# atxmega64.net
KiCad netlist of a schematic drawn in Altium Designer
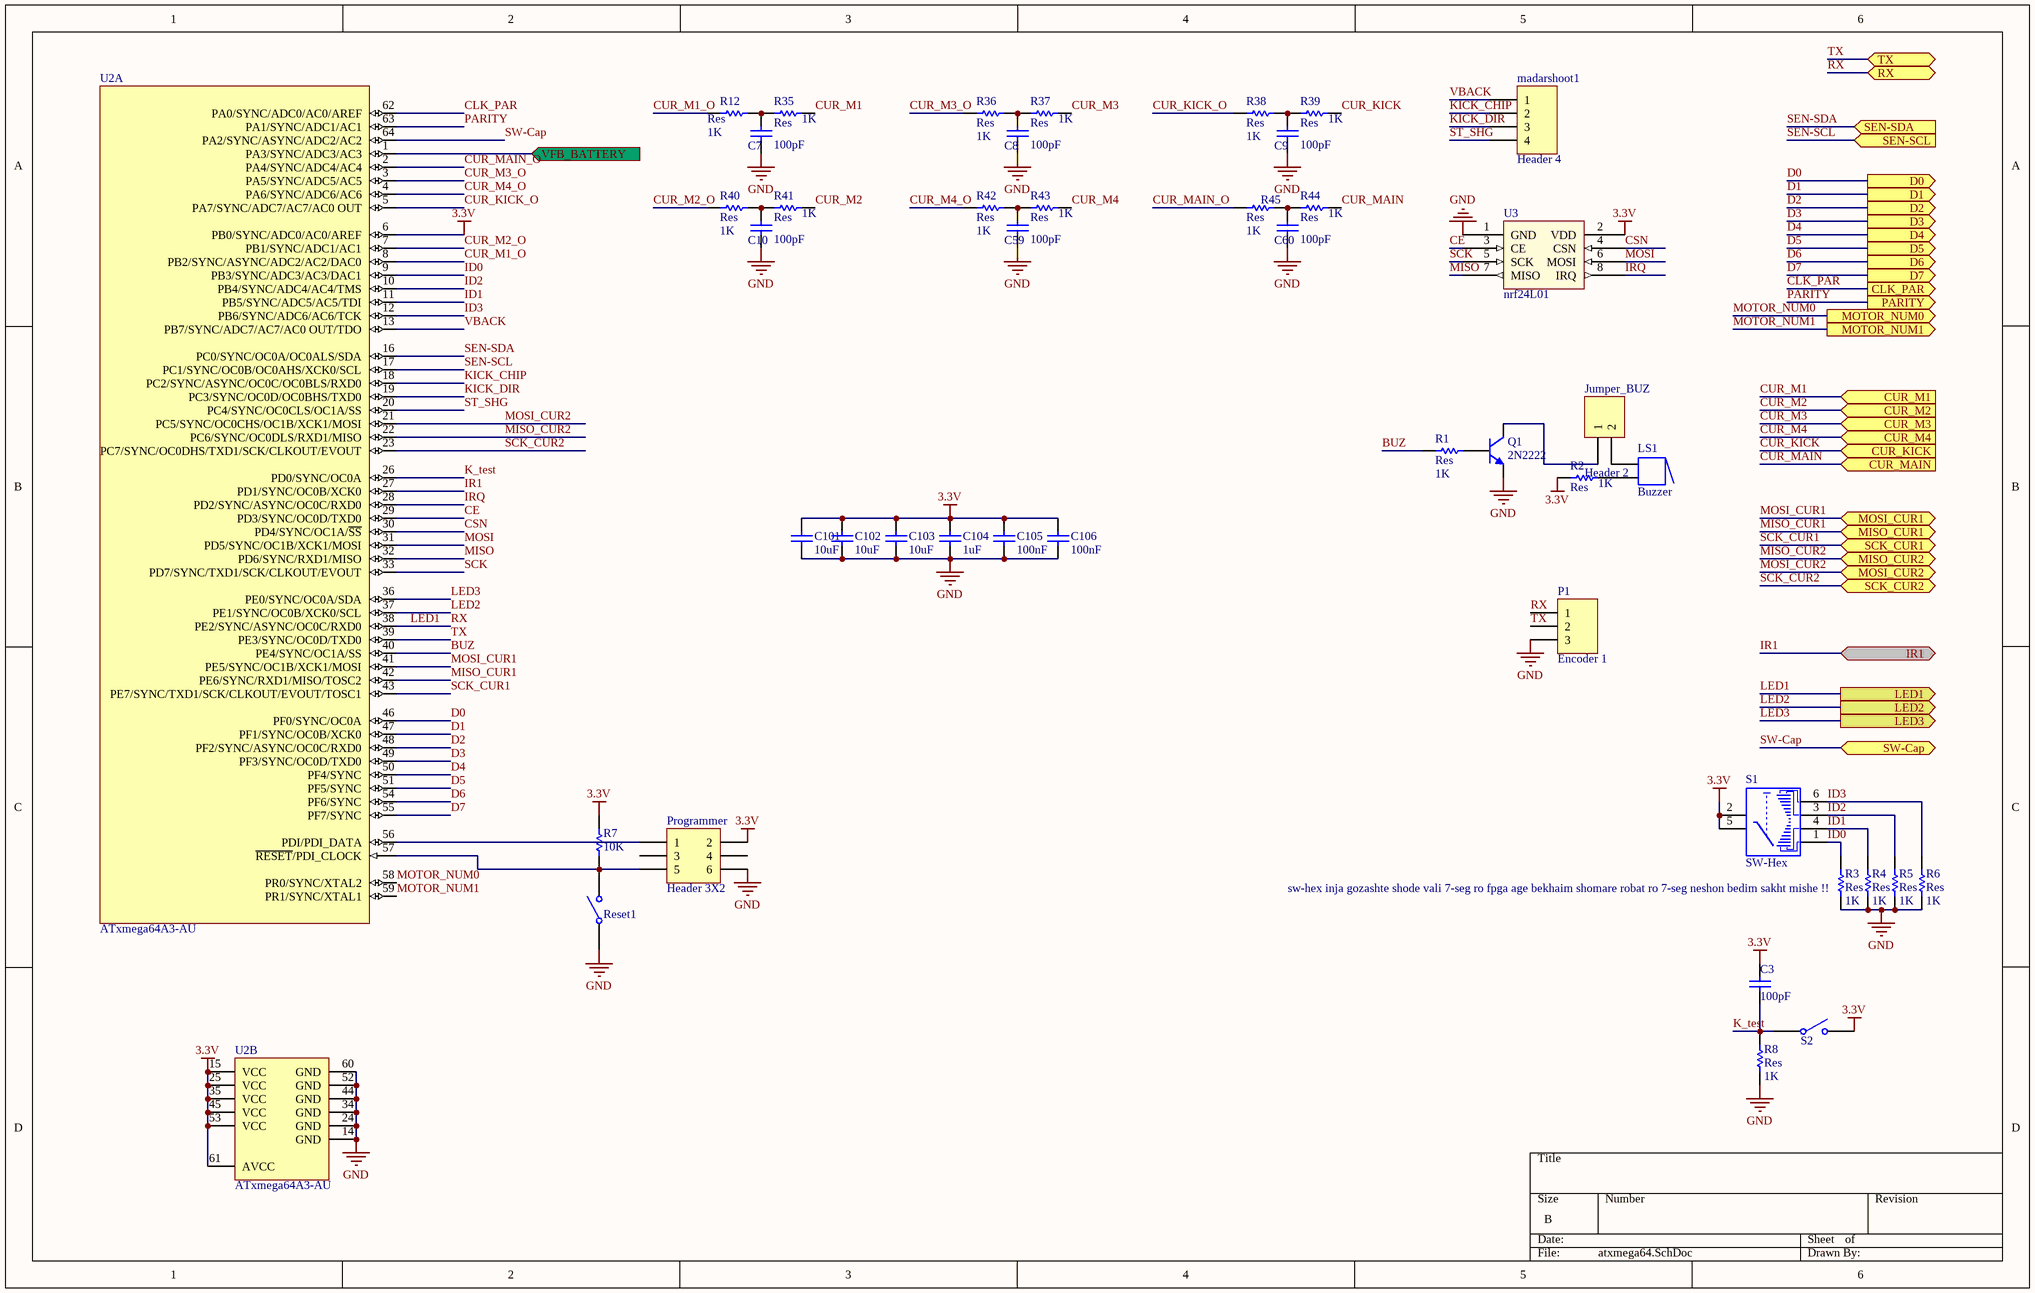
[diagram p0: atxmega64.SchDoc]

(export (version "E")
  (design (tool "Eeschema 10.0.6"))
  (components
    (comp (ref "C3")
      (value "100pF")
      (footprint "2012[0805]")
      (description "Capacitor")
      (fields (field (name "Comment") "Cap_UP") (field (name "PUBLISHER") "Altium Limited"))
      (libsource (lib "KN2CLib") (part "Cap_UP"))
    )
    (comp (ref "C7")
      (value "100pF")
      (footprint "2012[0805]")
      (description "Capacitor")
      (fields (field (name "Comment") "Cap_UP") (field (name "PUBLISHER") "Altium Limited"))
      (libsource (lib "KN2CLib") (part "Cap_UP"))
    )
    (comp (ref "C8")
      (value "100pF")
      (footprint "2012[0805]")
      (description "Capacitor")
      (fields (field (name "Comment") "Cap_UP") (field (name "PUBLISHER") "Altium Limited"))
      (libsource (lib "KN2CLib") (part "Cap_UP"))
    )
    (comp (ref "C9")
      (value "100pF")
      (footprint "2012[0805]")
      (description "Capacitor")
      (fields (field (name "Comment") "Cap_UP") (field (name "PUBLISHER") "Altium Limited"))
      (libsource (lib "KN2CLib") (part "Cap_UP"))
    )
    (comp (ref "C10")
      (value "100pF")
      (footprint "2012[0805]")
      (description "Capacitor")
      (fields (field (name "Comment") "Cap_UP") (field (name "PUBLISHER") "Altium Limited"))
      (libsource (lib "KN2CLib") (part "Cap_UP"))
    )
    (comp (ref "C59")
      (value "100pF")
      (footprint "2012[0805]")
      (description "Capacitor")
      (fields (field (name "Comment") "Cap_UP") (field (name "PUBLISHER") "Altium Limited"))
      (libsource (lib "KN2CLib") (part "Cap_UP"))
    )
    (comp (ref "C60")
      (value "100pF")
      (footprint "2012[0805]")
      (description "Capacitor")
      (fields (field (name "Comment") "Cap_UP") (field (name "PUBLISHER") "Altium Limited"))
      (libsource (lib "KN2CLib") (part "Cap_UP"))
    )
    (comp (ref "C101")
      (value "10uF")
      (footprint "2012[0805]")
      (description "Capacitor")
      (fields (field (name "Comment") "Cap_UP") (field (name "PUBLISHER") "Altium Limited"))
      (libsource (lib "KN2CLib") (part "Cap_UP"))
    )
    (comp (ref "C102")
      (value "10uF")
      (footprint "2012[0805]")
      (description "Capacitor")
      (fields (field (name "Comment") "Cap_UP") (field (name "PUBLISHER") "Altium Limited"))
      (libsource (lib "KN2CLib") (part "Cap_UP"))
    )
    (comp (ref "C103")
      (value "10uF")
      (footprint "2012[0805]")
      (description "Capacitor")
      (fields (field (name "Comment") "Cap_UP") (field (name "PUBLISHER") "Altium Limited"))
      (libsource (lib "KN2CLib") (part "Cap_UP"))
    )
    (comp (ref "C104")
      (value "1uF")
      (footprint "2012[0805]")
      (description "Capacitor")
      (fields (field (name "Comment") "Cap_UP") (field (name "PUBLISHER") "Altium Limited"))
      (libsource (lib "KN2CLib") (part "Cap_UP"))
    )
    (comp (ref "C105")
      (value "100nF")
      (footprint "2012[0805]")
      (description "Capacitor")
      (fields (field (name "Comment") "Cap_UP") (field (name "PUBLISHER") "Altium Limited"))
      (libsource (lib "KN2CLib") (part "Cap_UP"))
    )
    (comp (ref "C106")
      (value "100nF")
      (footprint "2012[0805]")
      (description "Capacitor")
      (fields (field (name "Comment") "Cap_UP") (field (name "PUBLISHER") "Altium Limited"))
      (libsource (lib "KN2CLib") (part "Cap_UP"))
    )
    (comp (ref "Jumper_BUZ")
      (value "Header 2")
      (footprint "HDR1X2")
      (description "Header, 2-Pin")
      (fields (field (name "PUBLISHER") "Altium Limited"))
      (libsource (lib "Miscellaneous Connectors") (part "Header 2"))
    )
    (comp (ref "LS1")
      (value "Buzzer")
      (footprint "BUZZER")
      (description "Magnetic Transducer Buzzer")
      (fields (field (name "PUBLISHER") "Altium Limited"))
      (libsource (lib "KN2CLib") (part "Buzzer"))
    )
    (comp (ref "madarshoot1")
      (value "Header 4")
      (footprint "sucket-smd-4pin")
      (description "Header, 4-Pin")
      (fields (field (name "PUBLISHER") "Altium Limited"))
      (libsource (lib "KN2CLib") (part "Header 4"))
    )
    (comp (ref "P1")
      (value "Encoder 1")
      (footprint "HDR1X3A")
      (description "Header, 3-Pin")
      (fields (field (name "PUBLISHER") "Altium Limited"))
      (libsource (lib "KN2CLib") (part "Header 3"))
    )
    (comp (ref "Programmer")
      (value "Header 3X2")
      (footprint "HDRBOX2X3")
      (description "Header, 3-Pin, Dual row")
      (fields (field (name "PUBLISHER") "Altium Limited"))
      (libsource (lib "KN2CLib") (part "Header 3X2"))
    )
    (comp (ref "Q1")
      (value "2N2222")
      (footprint "SOT-23")
      (description "NPN Bipolar Transistor")
      (fields (field (name "PUBLISHER") "Altium Limited"))
      (libsource (lib "KN2CLib") (part "2N2222"))
    )
    (comp (ref "R1")
      (value "Res")
      (footprint "2012[0805]")
      (description "Semiconductor Resistor")
      (fields (field (name "ALTIUM_VALUE") "1K") (field (name "PUBLISHER") "Altium Limited"))
      (libsource (lib "KN2CLib") (part "Res"))
    )
    (comp (ref "R2")
      (value "Res")
      (footprint "2012[0805]")
      (description "Semiconductor Resistor")
      (fields (field (name "ALTIUM_VALUE") "1K") (field (name "PUBLISHER") "Altium Limited"))
      (libsource (lib "KN2CLib") (part "Res"))
    )
    (comp (ref "R3")
      (value "Res")
      (footprint "2012[0805]")
      (description "Semiconductor Resistor")
      (fields (field (name "ALTIUM_VALUE") "1K") (field (name "PUBLISHER") "Altium Limited"))
      (libsource (lib "KN2CLib") (part "Res"))
    )
    (comp (ref "R4")
      (value "Res")
      (footprint "2012[0805]")
      (description "Semiconductor Resistor")
      (fields (field (name "ALTIUM_VALUE") "1K") (field (name "PUBLISHER") "Altium Limited"))
      (libsource (lib "KN2CLib") (part "Res"))
    )
    (comp (ref "R5")
      (value "Res")
      (footprint "2012[0805]")
      (description "Semiconductor Resistor")
      (fields (field (name "ALTIUM_VALUE") "1K") (field (name "PUBLISHER") "Altium Limited"))
      (libsource (lib "KN2CLib") (part "Res"))
    )
    (comp (ref "R6")
      (value "Res")
      (footprint "2012[0805]")
      (description "Semiconductor Resistor")
      (fields (field (name "ALTIUM_VALUE") "1K") (field (name "PUBLISHER") "Altium Limited"))
      (libsource (lib "KN2CLib") (part "Res"))
    )
    (comp (ref "R7")
      (value "10K")
      (footprint "2012[0805]")
      (description "Semiconductor Resistor")
      (fields (field (name "PUBLISHER") "Altium Limited"))
      (libsource (lib "KN2CLib") (part "Res"))
    )
    (comp (ref "R8")
      (value "Res")
      (footprint "2012[0805]")
      (description "Semiconductor Resistor")
      (fields (field (name "ALTIUM_VALUE") "1K") (field (name "PUBLISHER") "Altium Limited"))
      (libsource (lib "KN2CLib") (part "Res"))
    )
    (comp (ref "R12")
      (value "Res")
      (footprint "2012[0805]")
      (description "Semiconductor Resistor")
      (fields (field (name "ALTIUM_VALUE") "1K") (field (name "PUBLISHER") "Altium Limited"))
      (libsource (lib "KN2CLib") (part "Res"))
    )
    (comp (ref "R35")
      (value "Res")
      (footprint "2012[0805]")
      (description "Semiconductor Resistor")
      (fields (field (name "ALTIUM_VALUE") "1K") (field (name "PUBLISHER") "Altium Limited"))
      (libsource (lib "KN2CLib") (part "Res"))
    )
    (comp (ref "R36")
      (value "Res")
      (footprint "2012[0805]")
      (description "Semiconductor Resistor")
      (fields (field (name "ALTIUM_VALUE") "1K") (field (name "PUBLISHER") "Altium Limited"))
      (libsource (lib "KN2CLib") (part "Res"))
    )
    (comp (ref "R37")
      (value "Res")
      (footprint "2012[0805]")
      (description "Semiconductor Resistor")
      (fields (field (name "ALTIUM_VALUE") "1K") (field (name "PUBLISHER") "Altium Limited"))
      (libsource (lib "KN2CLib") (part "Res"))
    )
    (comp (ref "R38")
      (value "Res")
      (footprint "2012[0805]")
      (description "Semiconductor Resistor")
      (fields (field (name "ALTIUM_VALUE") "1K") (field (name "PUBLISHER") "Altium Limited"))
      (libsource (lib "KN2CLib") (part "Res"))
    )
    (comp (ref "R39")
      (value "Res")
      (footprint "2012[0805]")
      (description "Semiconductor Resistor")
      (fields (field (name "ALTIUM_VALUE") "1K") (field (name "PUBLISHER") "Altium Limited"))
      (libsource (lib "KN2CLib") (part "Res"))
    )
    (comp (ref "R40")
      (value "Res")
      (footprint "2012[0805]")
      (description "Semiconductor Resistor")
      (fields (field (name "ALTIUM_VALUE") "1K") (field (name "PUBLISHER") "Altium Limited"))
      (libsource (lib "KN2CLib") (part "Res"))
    )
    (comp (ref "R41")
      (value "Res")
      (footprint "2012[0805]")
      (description "Semiconductor Resistor")
      (fields (field (name "ALTIUM_VALUE") "1K") (field (name "PUBLISHER") "Altium Limited"))
      (libsource (lib "KN2CLib") (part "Res"))
    )
    (comp (ref "R42")
      (value "Res")
      (footprint "2012[0805]")
      (description "Semiconductor Resistor")
      (fields (field (name "ALTIUM_VALUE") "1K") (field (name "PUBLISHER") "Altium Limited"))
      (libsource (lib "KN2CLib") (part "Res"))
    )
    (comp (ref "R43")
      (value "Res")
      (footprint "2012[0805]")
      (description "Semiconductor Resistor")
      (fields (field (name "ALTIUM_VALUE") "1K") (field (name "PUBLISHER") "Altium Limited"))
      (libsource (lib "KN2CLib") (part "Res"))
    )
    (comp (ref "R44")
      (value "Res")
      (footprint "2012[0805]")
      (description "Semiconductor Resistor")
      (fields (field (name "ALTIUM_VALUE") "1K") (field (name "PUBLISHER") "Altium Limited"))
      (libsource (lib "KN2CLib") (part "Res"))
    )
    (comp (ref "R45")
      (value "Res")
      (footprint "2012[0805]")
      (description "Semiconductor Resistor")
      (fields (field (name "ALTIUM_VALUE") "1K") (field (name "PUBLISHER") "Altium Limited"))
      (libsource (lib "KN2CLib") (part "Res"))
    )
    (comp (ref "Reset1")
      (value "SW-SPST")
      (footprint "PUSH-BUT")
      (description "Single-Pole, Single-Throw Switch")
      (fields (field (name "PUBLISHER") "Altium Limited"))
      (libsource (lib "KN2CLib") (part "SW-SPST"))
    )
    (comp (ref "S1")
      (value "SW-Hex")
      (footprint "SW-HEX")
      (fields (field (name "PUBLISHER") "Altium Limited"))
      (libsource (lib "KN2CLib") (part "SW-Hex"))
    )
    (comp (ref "S2")
      (value "SW-SPST")
      (footprint "PUSH-BUT")
      (description "Single-Pole, Single-Throw Switch")
      (fields (field (name "PUBLISHER") "Altium Limited"))
      (libsource (lib "KN2CLib") (part "SW-SPST"))
    )
    (comp (ref "U2")
      (value "ATxmega64A3-AU")
      (footprint "64A_N")
      (fields (field (name "PUBLISHER") "Altium Limited"))
      (libsource (lib "Atmel Microcontroller 8-16-Bit AVR XMEGA") (part "ATxmega64A3-AU"))
    )
    (comp (ref "U3") (value "nrf24L01") (footprint "NRF24L01") (libsource (lib "KN2CLib") (part "nrf24L01")))
  )
  (nets
    (net (code "1") (name "/BUZ") (class "Default")
      (node (ref "R1") (pin "1") (pinfunction "1_1") (pintype "passive"))
      (node (ref "U2") (pin "40") (pinfunction "PE4/SYNC/OC1A/SS_40") (pintype "bidirectional"))
    )
    (net (code "2") (name "/CE") (class "Default")
      (node (ref "U2") (pin "29") (pinfunction "PD3/SYNC/OC0D/TXD0_29") (pintype "bidirectional"))
      (node (ref "U3") (pin "3") (pinfunction "CE_3") (pintype "input"))
    )
    (net (code "3") (name "/CLK_PAR") (class "Default")
      (node (ref "U2") (pin "62") (pinfunction "PA0/SYNC/ADC0/AC0/AREF_62") (pintype "bidirectional"))
    )
    (net (code "4") (name "/CSN") (class "Default")
      (node (ref "U2") (pin "30") (pinfunction "PD4/SYNC/OC1A/~{SS}_30") (pintype "bidirectional"))
      (node (ref "U3") (pin "4") (pinfunction "CSN_4") (pintype "input"))
    )
    (net (code "5") (name "/CUR_KICK") (class "Default")
      (node (ref "R39") (pin "2") (pinfunction "2_2") (pintype "passive"))
    )
    (net (code "6") (name "/CUR_KICK_O") (class "Default")
      (node (ref "R38") (pin "1") (pinfunction "1_1") (pintype "passive"))
      (node (ref "U2") (pin "5") (pinfunction "PA7/SYNC/ADC7/AC7/AC0_OUT_5") (pintype "bidirectional"))
    )
    (net (code "7") (name "/CUR_M1") (class "Default")
      (node (ref "R35") (pin "2") (pinfunction "2_2") (pintype "passive"))
    )
    (net (code "8") (name "/CUR_M1_O") (class "Default")
      (node (ref "R12") (pin "1") (pinfunction "1_1") (pintype "passive"))
      (node (ref "U2") (pin "8") (pinfunction "PB2/SYNC/ASYNC/ADC2/AC2/DAC0_8") (pintype "bidirectional"))
    )
    (net (code "9") (name "/CUR_M2") (class "Default")
      (node (ref "R41") (pin "2") (pinfunction "2_2") (pintype "passive"))
    )
    (net (code "10") (name "/CUR_M2_O") (class "Default")
      (node (ref "R40") (pin "1") (pinfunction "1_1") (pintype "passive"))
      (node (ref "U2") (pin "7") (pinfunction "PB1/SYNC/ADC1/AC1_7") (pintype "bidirectional"))
    )
    (net (code "11") (name "/CUR_M3") (class "Default")
      (node (ref "R37") (pin "2") (pinfunction "2_2") (pintype "passive"))
    )
    (net (code "12") (name "/CUR_M3_O") (class "Default")
      (node (ref "R36") (pin "1") (pinfunction "1_1") (pintype "passive"))
      (node (ref "U2") (pin "3") (pinfunction "PA5/SYNC/ADC5/AC5_3") (pintype "bidirectional"))
    )
    (net (code "13") (name "/CUR_M4") (class "Default")
      (node (ref "R43") (pin "2") (pinfunction "2_2") (pintype "passive"))
    )
    (net (code "14") (name "/CUR_M4_O") (class "Default")
      (node (ref "R42") (pin "1") (pinfunction "1_1") (pintype "passive"))
      (node (ref "U2") (pin "4") (pinfunction "PA6/SYNC/ADC6/AC6_4") (pintype "bidirectional"))
    )
    (net (code "15") (name "/CUR_MAIN") (class "Default")
      (node (ref "R44") (pin "2") (pinfunction "2_2") (pintype "passive"))
    )
    (net (code "16") (name "/CUR_MAIN_O") (class "Default")
      (node (ref "R45") (pin "1") (pinfunction "1_1") (pintype "passive"))
      (node (ref "U2") (pin "2") (pinfunction "PA4/SYNC/ADC4/AC4_2") (pintype "bidirectional"))
    )
    (net (code "17") (name "/D0") (class "Default")
      (node (ref "U2") (pin "46") (pinfunction "PF0/SYNC/OC0A_46") (pintype "bidirectional"))
    )
    (net (code "18") (name "/D1") (class "Default")
      (node (ref "U2") (pin "47") (pinfunction "PF1/SYNC/OC0B/XCK0_47") (pintype "bidirectional"))
    )
    (net (code "19") (name "/D2") (class "Default")
      (node (ref "U2") (pin "48") (pinfunction "PF2/SYNC/ASYNC/OC0C/RXD0_48") (pintype "bidirectional"))
    )
    (net (code "20") (name "/D3") (class "Default")
      (node (ref "U2") (pin "49") (pinfunction "PF3/SYNC/OC0D/TXD0_49") (pintype "bidirectional"))
    )
    (net (code "21") (name "/D4") (class "Default")
      (node (ref "U2") (pin "50") (pinfunction "PF4/SYNC_50") (pintype "bidirectional"))
    )
    (net (code "22") (name "/D5") (class "Default")
      (node (ref "U2") (pin "51") (pinfunction "PF5/SYNC_51") (pintype "bidirectional"))
    )
    (net (code "23") (name "/D6") (class "Default")
      (node (ref "U2") (pin "54") (pinfunction "PF6/SYNC_54") (pintype "bidirectional"))
    )
    (net (code "24") (name "/D7") (class "Default")
      (node (ref "U2") (pin "55") (pinfunction "PF7/SYNC_55") (pintype "bidirectional"))
    )
    (net (code "25") (name "/ID0") (class "Default")
      (node (ref "R3") (pin "2") (pinfunction "2_2") (pintype "passive"))
      (node (ref "S1") (pin "1") (pinfunction "1_1") (pintype "passive"))
      (node (ref "U2") (pin "9") (pinfunction "PB3/SYNC/ADC3/AC3/DAC1_9") (pintype "bidirectional"))
    )
    (net (code "26") (name "/ID1") (class "Default")
      (node (ref "R4") (pin "2") (pinfunction "2_2") (pintype "passive"))
      (node (ref "S1") (pin "4") (pinfunction "4_4") (pintype "passive"))
      (node (ref "U2") (pin "11") (pinfunction "PB5/SYNC/ADC5/AC5/TDI_11") (pintype "bidirectional"))
    )
    (net (code "27") (name "/ID2") (class "Default")
      (node (ref "R5") (pin "2") (pinfunction "2_2") (pintype "passive"))
      (node (ref "S1") (pin "3") (pinfunction "3_3") (pintype "passive"))
      (node (ref "U2") (pin "10") (pinfunction "PB4/SYNC/ADC4/AC4/TMS_10") (pintype "bidirectional"))
    )
    (net (code "28") (name "/ID3") (class "Default")
      (node (ref "R6") (pin "2") (pinfunction "2_2") (pintype "passive"))
      (node (ref "S1") (pin "6") (pinfunction "6_6") (pintype "passive"))
      (node (ref "U2") (pin "12") (pinfunction "PB6/SYNC/ADC6/AC6/TCK_12") (pintype "bidirectional"))
    )
    (net (code "29") (name "/IR1") (class "Default")
      (node (ref "U2") (pin "27") (pinfunction "PD1/SYNC/OC0B/XCK0_27") (pintype "bidirectional"))
    )
    (net (code "30") (name "/IRQ") (class "Default")
      (node (ref "U2") (pin "28") (pinfunction "PD2/SYNC/ASYNC/OC0C/RXD0_28") (pintype "bidirectional"))
      (node (ref "U3") (pin "8") (pinfunction "IRQ_8") (pintype "output"))
    )
    (net (code "31") (name "/KICK_CHIP") (class "Default")
      (node (ref "U2") (pin "18") (pinfunction "PC2/SYNC/ASYNC/OC0C/OC0BLS/RXD0_18") (pintype "bidirectional"))
      (node (ref "madarshoot1") (pin "2") (pinfunction "2_2") (pintype "passive"))
    )
    (net (code "32") (name "/KICK_DIR") (class "Default")
      (node (ref "U2") (pin "19") (pinfunction "PC3/SYNC/OC0D/OC0BHS/TXD0_19") (pintype "bidirectional"))
      (node (ref "madarshoot1") (pin "3") (pinfunction "3_3") (pintype "passive"))
    )
    (net (code "33") (name "/K_test") (class "Default")
      (node (ref "C3") (pin "1") (pinfunction "1_1") (pintype "passive"))
      (node (ref "R8") (pin "1") (pinfunction "1_1") (pintype "passive"))
      (node (ref "S2") (pin "1") (pinfunction "COMMON_1") (pintype "passive"))
      (node (ref "U2") (pin "26") (pinfunction "PD0/SYNC/OC0A_26") (pintype "bidirectional"))
    )
    (net (code "34") (name "/LED1") (class "Default")
      (node (ref "P1") (pin "1") (pinfunction "1_1") (pintype "passive"))
      (node (ref "U2") (pin "38") (pinfunction "PE2/SYNC/ASYNC/OC0C/RXD0_38") (pintype "bidirectional"))
    )
    (net (code "35") (name "/LED2") (class "Default")
      (node (ref "U2") (pin "37") (pinfunction "PE1/SYNC/OC0B/XCK0/SCL_37") (pintype "bidirectional"))
    )
    (net (code "36") (name "/LED3") (class "Default")
      (node (ref "U2") (pin "36") (pinfunction "PE0/SYNC/OC0A/SDA_36") (pintype "bidirectional"))
    )
    (net (code "37") (name "/MISO") (class "Default")
      (node (ref "U2") (pin "32") (pinfunction "PD6/SYNC/RXD1/MISO_32") (pintype "bidirectional"))
      (node (ref "U3") (pin "7") (pinfunction "MISO_7") (pintype "output"))
    )
    (net (code "38") (name "/MISO_CUR1") (class "Default")
      (node (ref "U2") (pin "42") (pinfunction "PE6/SYNC/RXD1/MISO/TOSC2_42") (pintype "bidirectional"))
    )
    (net (code "39") (name "/MISO_CUR2") (class "Default")
      (node (ref "U2") (pin "22") (pinfunction "PC6/SYNC/OC0DLS/RXD1/MISO_22") (pintype "bidirectional"))
    )
    (net (code "40") (name "/MOSI") (class "Default")
      (node (ref "U2") (pin "31") (pinfunction "PD5/SYNC/OC1B/XCK1/MOSI_31") (pintype "bidirectional"))
      (node (ref "U3") (pin "6") (pinfunction "MOSI_6") (pintype "input"))
    )
    (net (code "41") (name "/MOSI_CUR1") (class "Default")
      (node (ref "U2") (pin "41") (pinfunction "PE5/SYNC/OC1B/XCK1/MOSI_41") (pintype "bidirectional"))
    )
    (net (code "42") (name "/MOSI_CUR2") (class "Default")
      (node (ref "U2") (pin "21") (pinfunction "PC5/SYNC/OC0CHS/OC1B/XCK1/MOSI_21") (pintype "bidirectional"))
    )
    (net (code "43") (name "/MOTOR_NUM0") (class "Default")
      (node (ref "U2") (pin "58") (pinfunction "PR0/SYNC/XTAL2_58") (pintype "bidirectional"))
    )
    (net (code "44") (name "/MOTOR_NUM1") (class "Default")
      (node (ref "U2") (pin "59") (pinfunction "PR1/SYNC/XTAL1_59") (pintype "bidirectional"))
    )
    (net (code "45") (name "/PARITY") (class "Default")
      (node (ref "U2") (pin "63") (pinfunction "PA1/SYNC/ADC1/AC1_63") (pintype "bidirectional"))
    )
    (net (code "46") (name "/SCK") (class "Default")
      (node (ref "U2") (pin "33") (pinfunction "PD7/SYNC/TXD1/SCK/CLKOUT/EVOUT_33") (pintype "bidirectional"))
      (node (ref "U3") (pin "5") (pinfunction "SCK_5") (pintype "input"))
    )
    (net (code "47") (name "/SCK_CUR1") (class "Default")
      (node (ref "U2") (pin "43") (pinfunction "PE7/SYNC/TXD1/SCK/CLKOUT/EVOUT/TOSC1_43") (pintype "bidirectional"))
    )
    (net (code "48") (name "/SCK_CUR2") (class "Default")
      (node (ref "U2") (pin "23") (pinfunction "PC7/SYNC/OC0DHS/TXD1/SCK/CLKOUT/EVOUT_23") (pintype "bidirectional"))
    )
    (net (code "49") (name "/SEN-SCL") (class "Default")
      (node (ref "U2") (pin "17") (pinfunction "PC1/SYNC/OC0B/OC0AHS/XCK0/SCL_17") (pintype "bidirectional"))
    )
    (net (code "50") (name "/SEN-SDA") (class "Default")
      (node (ref "U2") (pin "16") (pinfunction "PC0/SYNC/OC0A/OC0ALS/SDA_16") (pintype "bidirectional"))
    )
    (net (code "51") (name "/ST_SHG") (class "Default")
      (node (ref "U2") (pin "20") (pinfunction "PC4/SYNC/OC0CLS/OC1A/SS_20") (pintype "bidirectional"))
      (node (ref "madarshoot1") (pin "4") (pinfunction "4_4") (pintype "passive"))
    )
    (net (code "52") (name "/SW-Cap") (class "Default")
      (node (ref "U2") (pin "64") (pinfunction "PA2/SYNC/ASYNC/ADC2/AC2_64") (pintype "bidirectional"))
    )
    (net (code "53") (name "/TX") (class "Default")
      (node (ref "P1") (pin "2") (pinfunction "2_2") (pintype "passive"))
      (node (ref "U2") (pin "39") (pinfunction "PE3/SYNC/OC0D/TXD0_39") (pintype "bidirectional"))
    )
    (net (code "54") (name "/VBACK") (class "Default")
      (node (ref "U2") (pin "13") (pinfunction "PB7/SYNC/ADC7/AC7/AC0_OUT/TDO_13") (pintype "bidirectional"))
      (node (ref "madarshoot1") (pin "1") (pinfunction "1_1") (pintype "passive"))
    )
    (net (code "55") (name "/VFB_BATTERY") (class "Default")
      (node (ref "U2") (pin "1") (pinfunction "PA3/SYNC/ADC3/AC3_1") (pintype "bidirectional"))
    )
    (net (code "56") (name "3.3V") (class "Default")
      (node (ref "C101") (pin "2") (pinfunction "2_2") (pintype "passive"))
      (node (ref "C102") (pin "2") (pinfunction "2_2") (pintype "passive"))
      (node (ref "C103") (pin "2") (pinfunction "2_2") (pintype "passive"))
      (node (ref "C104") (pin "2") (pinfunction "2_2") (pintype "passive"))
      (node (ref "C105") (pin "2") (pinfunction "2_2") (pintype "passive"))
      (node (ref "C106") (pin "2") (pinfunction "2_2") (pintype "passive"))
      (node (ref "C3") (pin "2") (pinfunction "2_2") (pintype "passive"))
      (node (ref "Programmer") (pin "2") (pinfunction "2_2") (pintype "passive"))
      (node (ref "R2") (pin "1") (pinfunction "1_1") (pintype "passive"))
      (node (ref "R7") (pin "1") (pinfunction "1_1") (pintype "passive"))
      (node (ref "S1") (pin "2") (pinfunction "2_2") (pintype "passive"))
      (node (ref "S1") (pin "5") (pinfunction "5_5") (pintype "passive"))
      (node (ref "S2") (pin "2") (pinfunction "NO_2") (pintype "passive"))
      (node (ref "U2") (pin "15") (pinfunction "VCC_15") (pintype "power_in"))
      (node (ref "U2") (pin "25") (pinfunction "VCC_25") (pintype "power_in"))
      (node (ref "U2") (pin "35") (pinfunction "VCC_35") (pintype "power_in"))
      (node (ref "U2") (pin "45") (pinfunction "VCC_45") (pintype "power_in"))
      (node (ref "U2") (pin "53") (pinfunction "VCC_53") (pintype "power_in"))
      (node (ref "U2") (pin "6") (pinfunction "PB0/SYNC/ADC0/AC0/AREF_6") (pintype "bidirectional"))
      (node (ref "U2") (pin "61") (pinfunction "AVCC_61") (pintype "power_in"))
      (node (ref "U3") (pin "2") (pinfunction "VDD_2") (pintype "power_in"))
    )
    (net (code "57") (name "GND") (class "Default")
      (node (ref "C10") (pin "1") (pinfunction "1_1") (pintype "passive"))
      (node (ref "C101") (pin "1") (pinfunction "1_1") (pintype "passive"))
      (node (ref "C102") (pin "1") (pinfunction "1_1") (pintype "passive"))
      (node (ref "C103") (pin "1") (pinfunction "1_1") (pintype "passive"))
      (node (ref "C104") (pin "1") (pinfunction "1_1") (pintype "passive"))
      (node (ref "C105") (pin "1") (pinfunction "1_1") (pintype "passive"))
      (node (ref "C106") (pin "1") (pinfunction "1_1") (pintype "passive"))
      (node (ref "C59") (pin "1") (pinfunction "1_1") (pintype "passive"))
      (node (ref "C60") (pin "1") (pinfunction "1_1") (pintype "passive"))
      (node (ref "C7") (pin "1") (pinfunction "1_1") (pintype "passive"))
      (node (ref "C8") (pin "1") (pinfunction "1_1") (pintype "passive"))
      (node (ref "C9") (pin "1") (pinfunction "1_1") (pintype "passive"))
      (node (ref "P1") (pin "3") (pinfunction "3_3") (pintype "passive"))
      (node (ref "Programmer") (pin "6") (pinfunction "6_6") (pintype "passive"))
      (node (ref "Q1") (pin "3") (pinfunction "E_3") (pintype "passive"))
      (node (ref "R3") (pin "1") (pinfunction "1_1") (pintype "passive"))
      (node (ref "R4") (pin "1") (pinfunction "1_1") (pintype "passive"))
      (node (ref "R5") (pin "1") (pinfunction "1_1") (pintype "passive"))
      (node (ref "R6") (pin "1") (pinfunction "1_1") (pintype "passive"))
      (node (ref "R8") (pin "2") (pinfunction "2_2") (pintype "passive"))
      (node (ref "Reset1") (pin "1") (pinfunction "COMMON_1") (pintype "passive"))
      (node (ref "U2") (pin "14") (pinfunction "GND_14") (pintype "power_in"))
      (node (ref "U2") (pin "24") (pinfunction "GND_24") (pintype "power_in"))
      (node (ref "U2") (pin "34") (pinfunction "GND_34") (pintype "power_in"))
      (node (ref "U2") (pin "44") (pinfunction "GND_44") (pintype "power_in"))
      (node (ref "U2") (pin "52") (pinfunction "GND_52") (pintype "power_in"))
      (node (ref "U2") (pin "60") (pinfunction "GND_60") (pintype "power_in"))
      (node (ref "U3") (pin "1") (pinfunction "GND_1") (pintype "power_in"))
    )
    (net (code "58") (name "Net-(C7-Pad2)") (class "Default")
      (node (ref "C7") (pin "2") (pinfunction "2_2") (pintype "passive"))
      (node (ref "R12") (pin "2") (pinfunction "2_2") (pintype "passive"))
      (node (ref "R35") (pin "1") (pinfunction "1_1") (pintype "passive"))
    )
    (net (code "59") (name "Net-(C8-Pad2)") (class "Default")
      (node (ref "C8") (pin "2") (pinfunction "2_2") (pintype "passive"))
      (node (ref "R36") (pin "2") (pinfunction "2_2") (pintype "passive"))
      (node (ref "R37") (pin "1") (pinfunction "1_1") (pintype "passive"))
    )
    (net (code "60") (name "Net-(C9-Pad2)") (class "Default")
      (node (ref "C9") (pin "2") (pinfunction "2_2") (pintype "passive"))
      (node (ref "R38") (pin "2") (pinfunction "2_2") (pintype "passive"))
      (node (ref "R39") (pin "1") (pinfunction "1_1") (pintype "passive"))
    )
    (net (code "61") (name "Net-(C10-Pad2)") (class "Default")
      (node (ref "C10") (pin "2") (pinfunction "2_2") (pintype "passive"))
      (node (ref "R40") (pin "2") (pinfunction "2_2") (pintype "passive"))
      (node (ref "R41") (pin "1") (pinfunction "1_1") (pintype "passive"))
    )
    (net (code "62") (name "Net-(C59-Pad2)") (class "Default")
      (node (ref "C59") (pin "2") (pinfunction "2_2") (pintype "passive"))
      (node (ref "R42") (pin "2") (pinfunction "2_2") (pintype "passive"))
      (node (ref "R43") (pin "1") (pinfunction "1_1") (pintype "passive"))
    )
    (net (code "63") (name "Net-(C60-Pad2)") (class "Default")
      (node (ref "C60") (pin "2") (pinfunction "2_2") (pintype "passive"))
      (node (ref "R44") (pin "1") (pinfunction "1_1") (pintype "passive"))
      (node (ref "R45") (pin "2") (pinfunction "2_2") (pintype "passive"))
    )
    (net (code "64") (name "Net-(Jumper_BUZ-Pad2)") (class "Default")
      (node (ref "Jumper_BUZ") (pin "2") (pinfunction "2_2") (pintype "passive"))
      (node (ref "LS1") (pin "1") (pinfunction "1_1") (pintype "passive"))
    )
    (net (code "65") (name "Net-(LS1-Pad2)") (class "Default")
      (node (ref "LS1") (pin "2") (pinfunction "2_2") (pintype "passive"))
      (node (ref "R2") (pin "2") (pinfunction "2_2") (pintype "passive"))
    )
    (net (code "66") (name "Net-(Q1-B)") (class "Default")
      (node (ref "Q1") (pin "2") (pinfunction "B_2") (pintype "passive"))
      (node (ref "R1") (pin "2") (pinfunction "2_2") (pintype "passive"))
    )
    (net (code "67") (name "Net-(Q1-C)") (class "Default")
      (node (ref "Jumper_BUZ") (pin "1") (pinfunction "1_1") (pintype "passive"))
      (node (ref "Q1") (pin "1") (pinfunction "C_1") (pintype "passive"))
    )
    (net (code "68") (name "Net-(Reset1-NO)") (class "Default")
      (node (ref "Programmer") (pin "5") (pinfunction "5_5") (pintype "passive"))
      (node (ref "R7") (pin "2") (pinfunction "2_2") (pintype "passive"))
      (node (ref "Reset1") (pin "2") (pinfunction "NO_2") (pintype "passive"))
      (node (ref "U2") (pin "57") (pinfunction "~{RESET}/PDI_CLOCK_57") (pintype "input"))
    )
    (net (code "69") (name "Net-(U2A-PDI{slash}PDI_DATA)") (class "Default")
      (node (ref "Programmer") (pin "1") (pinfunction "1_1") (pintype "passive"))
      (node (ref "U2") (pin "56") (pinfunction "PDI/PDI_DATA_56") (pintype "bidirectional"))
    )
    (net (code "70") (name "unconnected-(Programmer-Pad3)") (class "Default")
      (node (ref "Programmer") (pin "3") (pinfunction "3_3") (pintype "passive"))
    )
    (net (code "71") (name "unconnected-(Programmer-Pad4)") (class "Default")
      (node (ref "Programmer") (pin "4") (pinfunction "4_4") (pintype "passive"))
    )
  )
)
